# Protection.net
KiCad netlist of a schematic drawn in Altium Designer
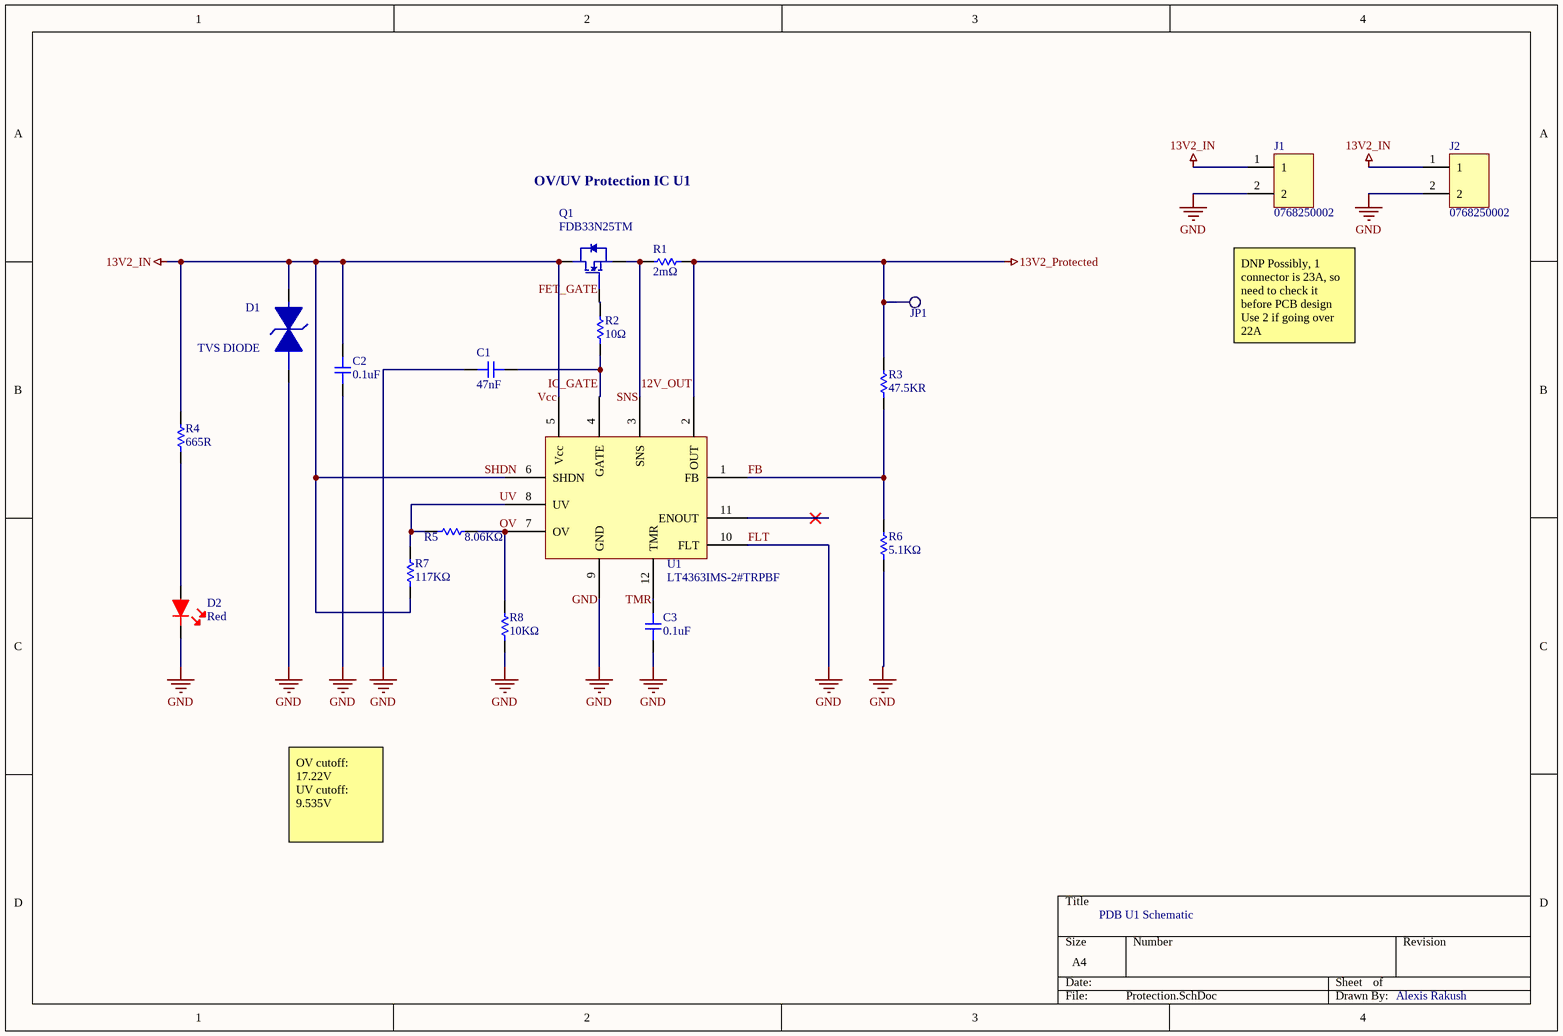
[diagram p0: Protection.SchDoc]

(export (version "E")
  (design (tool "Eeschema 10.0.6"))
  (components
    (comp (ref "C1")
      (value "47nF")
      (footprint "CAP-0603")
      (description "CAP CER 0.047UF 50V X7R 0603")
      (fields
        (field (name "MANUFACTURER") "Yageo")
        (field (name "MANUFACTURER PART NUMBER") "CC0603KRX7R9BB473")
      )
      (libsource (lib "Capacitors") (part "0603-47nF-50V"))
    )
    (comp (ref "C2")
      (value "0.1uF")
      (footprint "CAP-0805")
      (description "CAP CER 0.1UF 50V Y5V 0805")
      (fields
        (field (name "MANUFACTURER") "KEMET")
        (field (name "MANUFACTURER PART NUMBER") "C0805C104Z5VACTU")
      )
      (libsource (lib "Capacitors") (part "0805-0.1uF-50V"))
    )
    (comp (ref "C3")
      (value "0.1uF")
      (footprint "CAP-0603")
      (description "CAP CER 0.1UF 16V X7R 0603")
      (fields
        (field (name "MANUFACTURER") "KEMET")
        (field (name "MANUFACTURER PART NUMBER") "C0603C104M4RACTU")
      )
      (libsource (lib "Schlib1") (part "0603-0.1uF-16V"))
    )
    (comp (ref "D1")
      (value "TVS DIODE")
      (footprint "PDB:DIODE_TVS")
      (description "TVS DIODE 58VWM 93.6VC SMA")
      (fields (field (name "MANUFACTURER") "Diodes") (field (name "MANUFACTURER PART NUMBER") "SMAJ58A-13-F"))
      (libsource (lib "Schlib1") (part "SMAJ58A-13-F"))
    )
    (comp (ref "D2")
      (value "Red")
      (footprint "LED-0603")
      (description "LED RED CLEAR 0603 SMD")
      (fields
        (field (name "MANUFACTURER") "Wurth Electronics")
        (field (name "MANUFACTURER PART NUMBER") "150060RS75000")
      )
      (libsource (lib "Schlib1") (part "LED-Red"))
    )
    (comp (ref "J1")
      (value "0768250002")
      (footprint "2X1PIN")
      (description "CONN HEADER R/A 2POS")
      (fields (field (name "MANUFACTURER") "Molex") (field (name "MANUFACTURER PART NUMBER") "76825-0002"))
      (libsource (lib "Schlib1") (part "2X1PIN"))
    )
    (comp (ref "J2")
      (value "0768250002")
      (footprint "2X1PIN")
      (description "CONN HEADER R/A 2POS")
      (fields (field (name "MANUFACTURER") "Molex") (field (name "MANUFACTURER PART NUMBER") "76825-0002"))
      (libsource (lib "Schlib1") (part "2X1PIN"))
    )
    (comp (ref "JP1")
      (value "Testpoint2")
      (footprint "TP2")
      (description "Single layer pad TP")
      (libsource (lib "Misc") (part "Testpoint2"))
    )
    (comp (ref "Q1")
      (value "FDB33N25TM")
      (description "Trans MOSFET N-CH 250V 33A 3-Pin(2+Tab) D2PAK T/R")
      (fields (field (name "MANUFACTURER") "ON Semiconductor / Fairchild"))
      (libsource (lib "Schlib1") (part "FDB33N25TM"))
    )
    (comp (ref "R1")
      (value "2mΩ")
      (footprint "RES-0805")
      (description "RES 0.002 OHM 1% 1/2W 0805")
      (fields
        (field (name "MANUFACTURER") "Vishay Dale")
        (field (name "MANUFACTURER PART NUMBER") "CRCW08055K00FKTA")
      )
      (libsource (lib "Schlib1") (part "0805-2mR"))
    )
    (comp (ref "R2")
      (value "10Ω")
      (footprint "RES-0805")
      (description "RES SMD 10 OHM 1% 1/8W 0805")
      (fields
        (field (name "MANUFACTURER") "Yageo")
        (field (name "MANUFACTURER PART NUMBER") "RC0805FR-0710RL")
      )
      (libsource (lib "Schlib1") (part "0805-10R"))
    )
    (comp (ref "R3")
      (value "47.5KR")
      (description "SMD Chip Resistor, 0805 [2012 Metric], 475 kohm, CRCW e3 Series, 150 V, Thick Film, 125 mW")
      (fields
        (field (name "MANUFACTURER") "Vishay")
        (field (name "MANUFACTURER PART NUMBER") "CRCW0805475KFKEA")
      )
      (libsource (lib "Resistors") (part "0805-47.5KR"))
    )
    (comp (ref "R4")
      (value "665R")
      (footprint "RES-0603")
      (description "RES SMD 665 OHM 1% 1/10W 0603")
      (fields
        (field (name "MANUFACTURER") "Yageo")
        (field (name "MANUFACTURER PART NUMBER") "RC0603FR-07665RL")
      )
      (libsource (lib "Resistors") (part "0603-665R"))
    )
    (comp (ref "R5")
      (value "8.06KΩ")
      (footprint "RES-0603")
      (description "RES SMD 8.06K OHM 1% 1/10W 0603")
      (fields
        (field (name "MANUFACTURER") "Panasonic")
        (field (name "MANUFACTURER PART NUMBER") "ERJ-3EKF8061V")
      )
      (libsource (lib "Schlib1") (part "0603-8.06KR"))
    )
    (comp (ref "R6")
      (value "5.1KΩ")
      (description "RES SMD 5.1K OHM 1% 1/8W 0805")
      (fields
        (field (name "MANUFACTURER") "TE Connectivity")
        (field (name "MANUFACTURER PART NUMBER") "1623257-1")
      )
      (libsource (lib "Schlib1") (part "0805-5.1KR"))
    )
    (comp (ref "R7")
      (value "117KΩ")
      (description "RES 117K OHM 0.5% 1/10W 0603")
      (fields
        (field (name "MANUFACTURER") "Yageo")
        (field (name "MANUFACTURER PART NUMBER") "RT0603DRE07117KL")
      )
      (libsource (lib "Schlib1") (part "0603-117KR"))
    )
    (comp (ref "R8")
      (value "10KΩ")
      (footprint "RES-0805")
      (description "RES SMD 10K OHM 1% 1/8W 0805")
      (fields
        (field (name "MANUFACTURER") "Yageo")
        (field (name "MANUFACTURER PART NUMBER") "RC0805FR-0710KL")
      )
      (libsource (lib "Schlib1") (part "0805-10KR"))
    )
    (comp (ref "U1")
      (value "LT4363IMS-2#TRPBF")
      (description "IC SURGE STOPPER HV 12-MSOP")
      (fields (field (name "MANUFACTURER") "Analog Devices / Linear Technology"))
      (libsource (lib "Schlib1") (part "LT4363IMS-2#TRPBF"))
    )
  )
  (nets
    (net (code "1") (name "/FB") (class "Default")
      (node (ref "R3") (pin "1") (pinfunction "1_1") (pintype "passive"))
      (node (ref "R6") (pin "2") (pinfunction "2_2") (pintype "passive"))
      (node (ref "U1") (pin "1") (pinfunction "FB_1") (pintype "passive"))
    )
    (net (code "6") (name "/SNS") (class "Default")
      (node (ref "Q1") (pin "3") (pinfunction "3_3") (pintype "passive"))
      (node (ref "R1") (pin "2") (pinfunction "2_2") (pintype "passive"))
      (node (ref "U1") (pin "3") (pinfunction "SNS_3") (pintype "passive"))
    )
    (net (code "7") (name "/TMR") (class "Default")
      (node (ref "C3") (pin "2") (pinfunction "2_2") (pintype "passive"))
      (node (ref "U1") (pin "12") (pinfunction "TMR_12") (pintype "passive"))
    )
    (net (code "9") (name "13V2_IN") (class "Default")
      (node (ref "C2") (pin "2") (pinfunction "2_2") (pintype "passive"))
      (node (ref "D1") (pin "1") (pinfunction "1_1") (pintype "passive"))
      (node (ref "J1") (pin "1") (pinfunction "1_1") (pintype "passive"))
      (node (ref "J2") (pin "1") (pinfunction "1_1") (pintype "passive"))
      (node (ref "Q1") (pin "4") (pinfunction "4_4") (pintype "passive"))
      (node (ref "R4") (pin "2") (pinfunction "2_2") (pintype "passive"))
      (node (ref "R7") (pin "1") (pinfunction "1_1") (pintype "passive"))
      (node (ref "U1") (pin "5") (pinfunction "Vcc_5") (pintype "passive"))
      (node (ref "U1") (pin "6") (pinfunction "SHDN_6") (pintype "passive"))
    )
    (net (code "10") (name "13V2_Protected") (class "Default")
      (node (ref "JP1") (pin "1") (pinfunction "1_1") (pintype "passive"))
      (node (ref "R1") (pin "1") (pinfunction "1_1") (pintype "passive"))
      (node (ref "R3") (pin "2") (pinfunction "2_2") (pintype "passive"))
      (node (ref "U1") (pin "2") (pinfunction "OUT_2") (pintype "passive"))
    )
    (net (code "11") (name "GND") (class "Default")
      (node (ref "C1") (pin "1") (pinfunction "1_1") (pintype "passive"))
      (node (ref "C2") (pin "1") (pinfunction "1_1") (pintype "passive"))
      (node (ref "C3") (pin "1") (pinfunction "1_1") (pintype "passive"))
      (node (ref "D1") (pin "2") (pinfunction "2_2") (pintype "passive"))
      (node (ref "D2") (pin "2") (pinfunction "2_2") (pintype "passive"))
      (node (ref "J1") (pin "2") (pinfunction "2_2") (pintype "passive"))
      (node (ref "J2") (pin "2") (pinfunction "2_2") (pintype "passive"))
      (node (ref "R6") (pin "1") (pinfunction "1_1") (pintype "passive"))
      (node (ref "R8") (pin "1") (pinfunction "1_1") (pintype "passive"))
      (node (ref "U1") (pin "10") (pinfunction "FLT_10") (pintype "passive"))
      (node (ref "U1") (pin "9") (pinfunction "GND_9") (pintype "passive"))
    )
    (net (code "12") (name "Net-(D2-Pad1)") (class "Default")
      (node (ref "D2") (pin "1") (pinfunction "1_1") (pintype "passive"))
      (node (ref "R4") (pin "1") (pinfunction "1_1") (pintype "passive"))
    )
    (net (code "13") (name "Net-(Q1-Pad1)") (class "Default")
      (node (ref "Q1") (pin "1") (pinfunction "1_1") (pintype "passive"))
      (node (ref "R2") (pin "2") (pinfunction "2_2") (pintype "passive"))
    )
    (net (code "14") (name "Net-(U1-GATE)") (class "Default")
      (node (ref "C1") (pin "2") (pinfunction "2_2") (pintype "passive"))
      (node (ref "R2") (pin "1") (pinfunction "1_1") (pintype "passive"))
      (node (ref "U1") (pin "4") (pinfunction "GATE_4") (pintype "passive"))
    )
    (net (code "15") (name "Net-(U1-OV)") (class "Default")
      (node (ref "R5") (pin "2") (pinfunction "2_2") (pintype "passive"))
      (node (ref "R8") (pin "2") (pinfunction "2_2") (pintype "passive"))
      (node (ref "U1") (pin "7") (pinfunction "OV_7") (pintype "passive"))
    )
    (net (code "16") (name "Net-(U1-UV)") (class "Default")
      (node (ref "R5") (pin "1") (pinfunction "1_1") (pintype "passive"))
      (node (ref "R7") (pin "2") (pinfunction "2_2") (pintype "passive"))
      (node (ref "U1") (pin "8") (pinfunction "UV_8") (pintype "passive"))
    )
    (net (code "17") (name "unconnected-(U1-ENOUT-Pad11)") (class "Default")
      (node (ref "U1") (pin "11") (pinfunction "ENOUT_11") (pintype "passive"))
    )
  )
)
